# powerful.net
KiCad netlist of a schematic drawn in Altium Designer
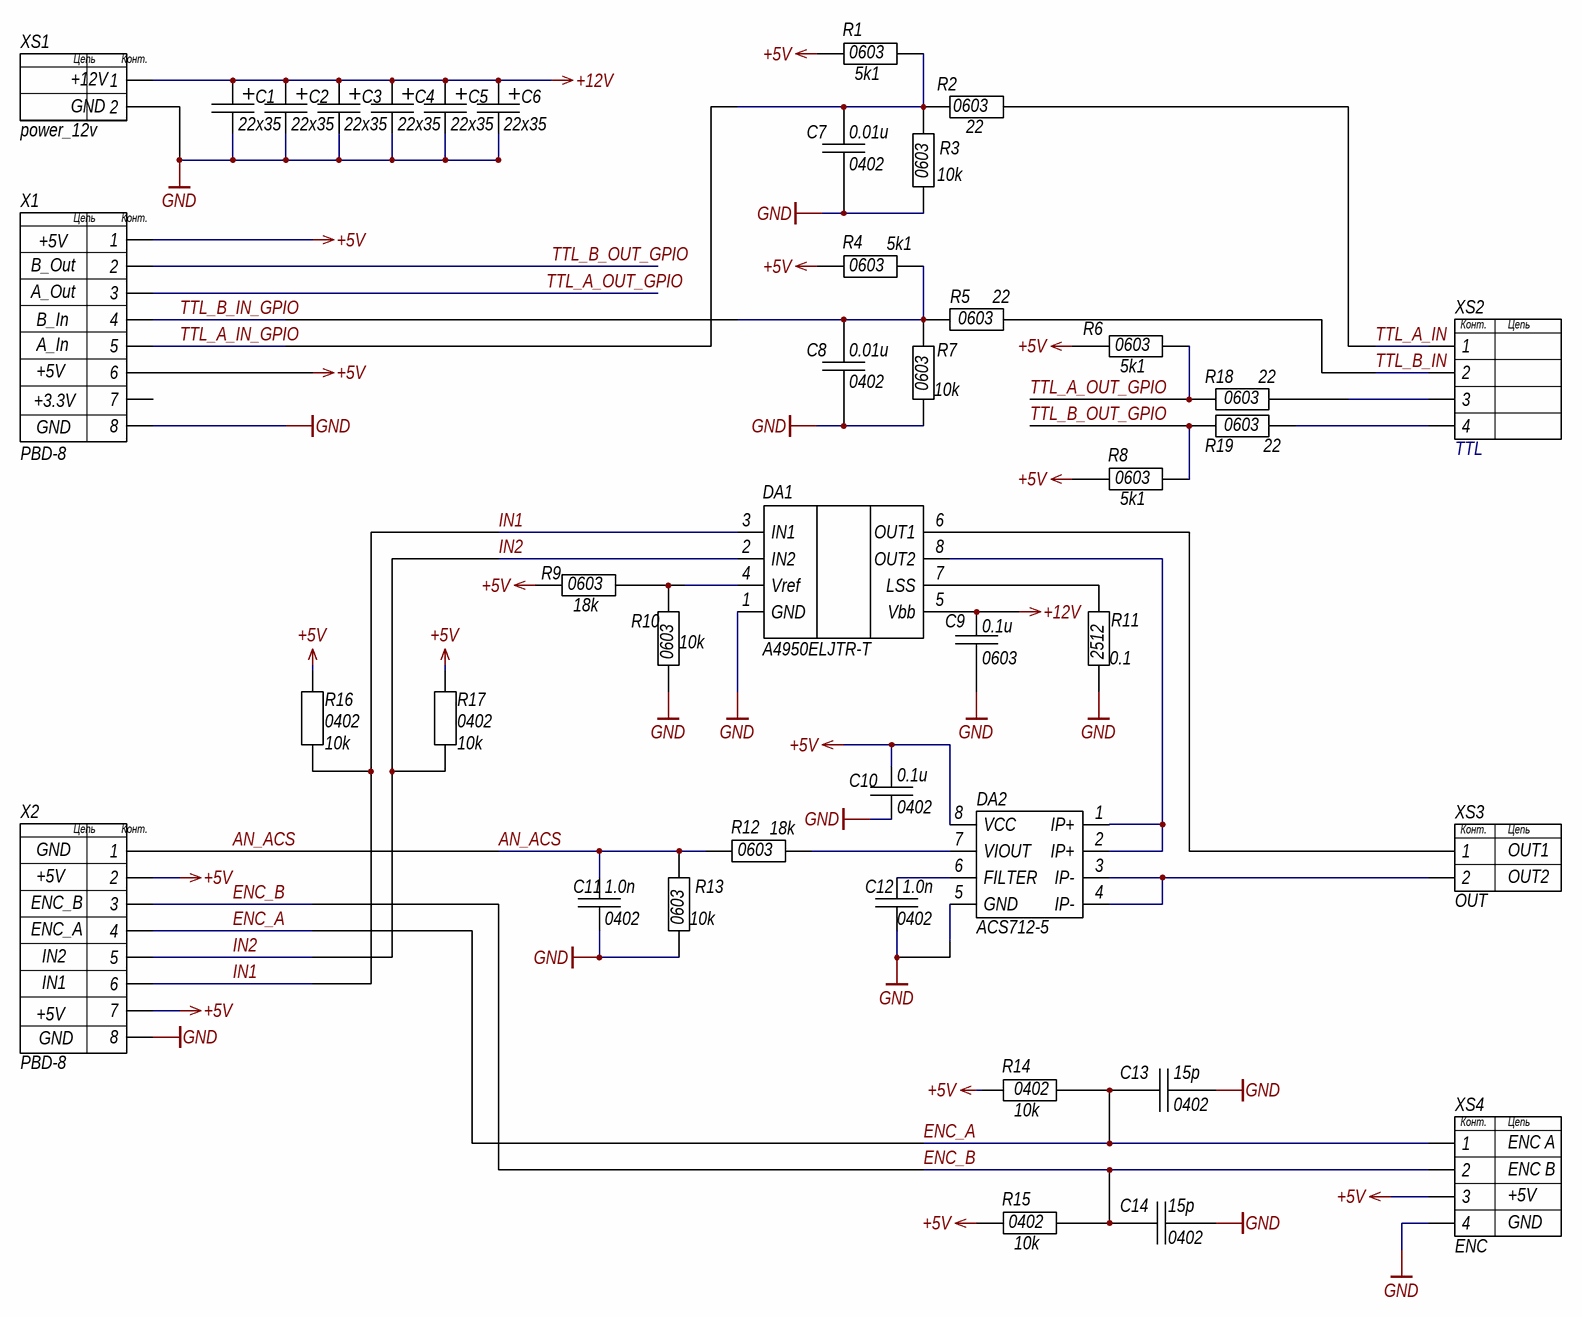
[diagram p0: powerful.SchDoc]

(export (version "E")
  (design (tool "Eeschema 10.0.6"))
  (components
    (comp (ref "C1")
      (value "22x35")
      (footprint "CASE D")
      (libsource (lib "Drive_GD32F") (part "Capacitor_pol"))
    )
    (comp (ref "C2")
      (value "22x35")
      (footprint "CASE D")
      (libsource (lib "Drive_GD32F") (part "Capacitor_pol"))
    )
    (comp (ref "C3")
      (value "22x35")
      (footprint "CASE D")
      (libsource (lib "Drive_GD32F") (part "Capacitor_pol"))
    )
    (comp (ref "C4")
      (value "22x35")
      (footprint "CASE D")
      (libsource (lib "Drive_GD32F") (part "Capacitor_pol"))
    )
    (comp (ref "C5")
      (value "22x35")
      (footprint "CASE D")
      (libsource (lib "Drive_GD32F") (part "Capacitor_pol"))
    )
    (comp (ref "C6")
      (value "22x35")
      (footprint "CASE D")
      (libsource (lib "Drive_GD32F") (part "Capacitor_pol"))
    )
    (comp (ref "C7")
      (value "0.01u")
      (footprint "0402_CAP")
      (fields (field (name "CASE") "0402"))
      (libsource (lib "Drive_GD32F") (part "Capacitor"))
    )
    (comp (ref "C8")
      (value "0.01u")
      (footprint "0402_CAP")
      (fields (field (name "CASE") "0402"))
      (libsource (lib "Drive_GD32F") (part "Capacitor"))
    )
    (comp (ref "C9")
      (value "0.1u")
      (footprint "0603_CAP")
      (fields (field (name "CASE") "0603"))
      (libsource (lib "Drive_GD32F") (part "Capacitor"))
    )
    (comp (ref "C10")
      (value "0.1u")
      (footprint "0402_CAP")
      (fields (field (name "CASE") "0402"))
      (libsource (lib "Drive_GD32F") (part "Capacitor"))
    )
    (comp (ref "C11")
      (value "1.0n")
      (footprint "0402_CAP")
      (fields (field (name "CASE") "0402"))
      (libsource (lib "Drive_GD32F") (part "Capacitor"))
    )
    (comp (ref "C12")
      (value "1.0n")
      (footprint "0402_CAP")
      (fields (field (name "CASE") "0402"))
      (libsource (lib "Drive_GD32F") (part "Capacitor"))
    )
    (comp (ref "C13")
      (value "15p")
      (footprint "0402_CAP")
      (fields (field (name "CASE") "0402"))
      (libsource (lib "Drive_GD32F") (part "Capacitor"))
    )
    (comp (ref "C14")
      (value "15p")
      (footprint "0402_CAP")
      (fields (field (name "CASE") "0402"))
      (libsource (lib "Drive_GD32F") (part "Capacitor"))
    )
    (comp (ref "DA1")
      (value "A4950ELJTR-T")
      (footprint "SOIC-8-ER")
      (libsource (lib "Drive_GD32F") (part "A4950ELJTR-T"))
    )
    (comp (ref "DA2")
      (value "ACS712-5")
      (footprint "SOIC-8")
      (libsource (lib "Drive_GD32F") (part "CurrentSensor_ACS712-5"))
    )
    (comp (ref "R1")
      (value "5k1")
      (footprint "0603_RES")
      (fields (field (name "CASE") "0603"))
      (libsource (lib "Drive_GD32F") (part "Resistor"))
    )
    (comp (ref "R2")
      (value "22")
      (footprint "0603_RES")
      (fields (field (name "POWER") "0603"))
      (libsource (lib "Drive_GD32F") (part "Resistor"))
    )
    (comp (ref "R3")
      (value "10k")
      (footprint "0603_RES")
      (fields (field (name "CASE") "0603"))
      (libsource (lib "Drive_GD32F") (part "Resistor"))
    )
    (comp (ref "R4")
      (value "5k1")
      (footprint "0603_RES")
      (fields (field (name "CASE") "0603"))
      (libsource (lib "Drive_GD32F") (part "Resistor"))
    )
    (comp (ref "R5")
      (value "22")
      (footprint "0603_RES")
      (fields (field (name "POWER") "0603"))
      (libsource (lib "Drive_GD32F") (part "Resistor"))
    )
    (comp (ref "R6")
      (value "5k1")
      (footprint "0603_RES")
      (fields (field (name "CASE") "0603"))
      (libsource (lib "Drive_GD32F") (part "Resistor"))
    )
    (comp (ref "R7")
      (value "10k")
      (footprint "0603_RES")
      (fields (field (name "CASE") "0603"))
      (libsource (lib "Drive_GD32F") (part "Resistor"))
    )
    (comp (ref "R8")
      (value "5k1")
      (footprint "0603_RES")
      (fields (field (name "CASE") "0603"))
      (libsource (lib "Drive_GD32F") (part "Resistor"))
    )
    (comp (ref "R9")
      (value "18k")
      (footprint "0603_RES")
      (fields (field (name "CASE") "0603"))
      (libsource (lib "Drive_GD32F") (part "Resistor"))
    )
    (comp (ref "R10")
      (value "10k")
      (footprint "0603_RES")
      (fields (field (name "CASE") "0603"))
      (libsource (lib "Drive_GD32F") (part "Resistor"))
    )
    (comp (ref "R11")
      (value "0.1")
      (footprint "2512_res")
      (fields (field (name "CASE") "2512"))
      (libsource (lib "Drive_GD32F") (part "Resistor"))
    )
    (comp (ref "R12")
      (value "18k")
      (footprint "0603_RES")
      (fields (field (name "CASE") "0603"))
      (libsource (lib "Drive_GD32F") (part "Resistor"))
    )
    (comp (ref "R13")
      (value "10k")
      (footprint "0603_RES")
      (fields (field (name "CASE") "0603"))
      (libsource (lib "Drive_GD32F") (part "Resistor"))
    )
    (comp (ref "R14")
      (value "10k")
      (footprint "0402_res")
      (fields (field (name "CASE") "0402"))
      (libsource (lib "Drive_GD32F") (part "Resistor"))
    )
    (comp (ref "R15")
      (value "10k")
      (footprint "0402_res")
      (fields (field (name "CASE") "0402"))
      (libsource (lib "Drive_GD32F") (part "Resistor"))
    )
    (comp (ref "R16")
      (value "10k")
      (footprint "0402_res")
      (fields (field (name "CASE") "0402"))
      (libsource (lib "Drive_GD32F") (part "Resistor"))
    )
    (comp (ref "R17")
      (value "10k")
      (footprint "0402_res")
      (fields (field (name "CASE") "0402"))
      (libsource (lib "Drive_GD32F") (part "Resistor"))
    )
    (comp (ref "R18")
      (value "22")
      (footprint "0603_RES")
      (fields (field (name "POWER") "0603"))
      (libsource (lib "Drive_GD32F") (part "Resistor"))
    )
    (comp (ref "R19")
      (value "22")
      (footprint "0603_RES")
      (fields (field (name "POWER") "0603"))
      (libsource (lib "Drive_GD32F") (part "Resistor"))
    )
    (comp (ref "X1")
      (value "PBD-8")
      (footprint "Header_8pin_2mm")
      (fields
        (field (name "PARAMETER 8") "GND")
        (field (name "PARAMETER 7") "+3.3V")
        (field (name "PARAMETER 6") "+5V")
        (field (name "PARAMETER 5") "A_In")
        (field (name "PARAMETER 4") "B_In")
        (field (name "PARAMETER 3") "A_Out")
        (field (name "PARAMETER 2") "B_Out")
        (field (name "PARAMETER 1") "+5V")
      )
      (libsource (lib "Drive_GD32F") (part "Connecor_8pin"))
    )
    (comp (ref "X2")
      (value "PBD-8")
      (footprint "Header_8pin_2mm")
      (fields
        (field (name "PARAMETER 8") "GND")
        (field (name "PARAMETER 7") "+5V")
        (field (name "PARAMETER 6") "IN1")
        (field (name "PARAMETER 5") "IN2")
        (field (name "PARAMETER 4") "ENC_A")
        (field (name "PARAMETER 3") "ENC_B")
        (field (name "PARAMETER 2") "+5V")
        (field (name "PARAMETER 1") "GND")
      )
      (libsource (lib "Drive_GD32F") (part "Connecor_8pin"))
    )
    (comp (ref "XS1")
      (value "power_12v")
      (footprint "STEP_2.54mm 2X1")
      (libsource (lib "Drive_GD32F") (part "power_12v"))
    )
    (comp (ref "XS2") (value "TTL") (footprint "PH4_2mm") (libsource (lib "Drive_GD32F") (part "TTL")))
    (comp (ref "XS3") (value "OUT") (footprint "step_2.54_2") (libsource (lib "Drive_GD32F") (part "OUT")))
    (comp (ref "XS4") (value "ENC") (footprint "PH4_2mm") (libsource (lib "Drive_GD32F") (part "ENC")))
  )
  (nets
    (net (code "1") (name "+5V") (class "Default")
      (node (ref "C10") (pin "2") (pintype "passive"))
      (node (ref "DA2") (pin "8") (pinfunction "VCC_8") (pintype "passive"))
      (node (ref "R1") (pin "2") (pinfunction "2_2") (pintype "passive"))
      (node (ref "R14") (pin "2") (pinfunction "2_2") (pintype "passive"))
      (node (ref "R15") (pin "2") (pinfunction "2_2") (pintype "passive"))
      (node (ref "R16") (pin "2") (pinfunction "2_2") (pintype "passive"))
      (node (ref "R17") (pin "2") (pinfunction "2_2") (pintype "passive"))
      (node (ref "R4") (pin "2") (pinfunction "2_2") (pintype "passive"))
      (node (ref "R6") (pin "2") (pinfunction "2_2") (pintype "passive"))
      (node (ref "R8") (pin "2") (pinfunction "2_2") (pintype "passive"))
      (node (ref "R9") (pin "2") (pinfunction "2_2") (pintype "passive"))
      (node (ref "X1") (pin "1") (pinfunction "1_1") (pintype "passive"))
      (node (ref "X1") (pin "6") (pinfunction "6_6") (pintype "passive"))
      (node (ref "X2") (pin "2") (pinfunction "2_2") (pintype "passive"))
      (node (ref "X2") (pin "7") (pinfunction "7_7") (pintype "passive"))
      (node (ref "XS4") (pin "3") (pinfunction "3_3") (pintype "passive"))
    )
    (net (code "2") (name "+12V") (class "Default")
      (node (ref "C1") (pin "1") (pintype "passive"))
      (node (ref "C2") (pin "1") (pintype "passive"))
      (node (ref "C3") (pin "1") (pintype "passive"))
      (node (ref "C4") (pin "1") (pintype "passive"))
      (node (ref "C5") (pin "1") (pintype "passive"))
      (node (ref "C6") (pin "1") (pintype "passive"))
      (node (ref "C9") (pin "1") (pintype "passive"))
      (node (ref "DA1") (pin "5") (pinfunction "Vbb_5") (pintype "passive"))
      (node (ref "XS1") (pin "1") (pinfunction "1_1") (pintype "passive"))
    )
    (net (code "3") (name "/AN_ACS") (class "Default")
      (node (ref "C11") (pin "2") (pintype "passive"))
      (node (ref "R12") (pin "1") (pinfunction "1_1") (pintype "passive"))
      (node (ref "R13") (pin "2") (pinfunction "2_2") (pintype "passive"))
      (node (ref "X2") (pin "1") (pinfunction "1_1") (pintype "passive"))
    )
    (net (code "4") (name "/ENC_A") (class "Default")
      (node (ref "C13") (pin "1") (pintype "passive"))
      (node (ref "R14") (pin "1") (pinfunction "1_1") (pintype "passive"))
      (node (ref "X2") (pin "4") (pinfunction "4_4") (pintype "passive"))
      (node (ref "XS4") (pin "1") (pinfunction "1_1") (pintype "passive"))
    )
    (net (code "5") (name "/ENC_B") (class "Default")
      (node (ref "C14") (pin "2") (pintype "passive"))
      (node (ref "R15") (pin "1") (pinfunction "1_1") (pintype "passive"))
      (node (ref "X2") (pin "3") (pinfunction "3_3") (pintype "passive"))
      (node (ref "XS4") (pin "2") (pinfunction "2_2") (pintype "passive"))
    )
    (net (code "6") (name "/IN1") (class "Default")
      (node (ref "DA1") (pin "3") (pinfunction "IN1_3") (pintype "passive"))
      (node (ref "R16") (pin "1") (pinfunction "1_1") (pintype "passive"))
      (node (ref "X2") (pin "6") (pinfunction "6_6") (pintype "passive"))
    )
    (net (code "7") (name "/IN2") (class "Default")
      (node (ref "DA1") (pin "2") (pinfunction "IN2_2") (pintype "passive"))
      (node (ref "R17") (pin "1") (pinfunction "1_1") (pintype "passive"))
      (node (ref "X2") (pin "5") (pinfunction "5_5") (pintype "passive"))
    )
    (net (code "8") (name "/TTL_A_IN") (class "Default")
      (node (ref "R2") (pin "2") (pinfunction "2_2") (pintype "passive"))
      (node (ref "XS2") (pin "1") (pinfunction "1_1") (pintype "passive"))
    )
    (net (code "9") (name "/TTL_A_IN_GPIO") (class "Default")
      (node (ref "C7") (pin "2") (pintype "passive"))
      (node (ref "R1") (pin "1") (pinfunction "1_1") (pintype "passive"))
      (node (ref "R2") (pin "1") (pinfunction "1_1") (pintype "passive"))
      (node (ref "R3") (pin "2") (pinfunction "2_2") (pintype "passive"))
      (node (ref "X1") (pin "5") (pinfunction "5_5") (pintype "passive"))
    )
    (net (code "10") (name "/TTL_A_OUT_GPIO") (class "Default")
      (node (ref "R18") (pin "1") (pinfunction "1_1") (pintype "passive"))
      (node (ref "R6") (pin "1") (pinfunction "1_1") (pintype "passive"))
      (node (ref "X1") (pin "3") (pinfunction "3_3") (pintype "passive"))
    )
    (net (code "11") (name "/TTL_B_IN") (class "Default")
      (node (ref "R5") (pin "2") (pinfunction "2_2") (pintype "passive"))
      (node (ref "XS2") (pin "2") (pinfunction "2_2") (pintype "passive"))
    )
    (net (code "12") (name "/TTL_B_IN_GPIO") (class "Default")
      (node (ref "C8") (pin "2") (pintype "passive"))
      (node (ref "R4") (pin "1") (pinfunction "1_1") (pintype "passive"))
      (node (ref "R5") (pin "1") (pinfunction "1_1") (pintype "passive"))
      (node (ref "R7") (pin "2") (pinfunction "2_2") (pintype "passive"))
      (node (ref "X1") (pin "4") (pinfunction "4_4") (pintype "passive"))
    )
    (net (code "13") (name "/TTL_B_OUT_GPIO") (class "Default")
      (node (ref "R19") (pin "1") (pinfunction "1_1") (pintype "passive"))
      (node (ref "R8") (pin "1") (pinfunction "1_1") (pintype "passive"))
      (node (ref "X1") (pin "2") (pinfunction "2_2") (pintype "passive"))
    )
    (net (code "14") (name "GND") (class "Default")
      (node (ref "C1") (pin "2") (pintype "passive"))
      (node (ref "C10") (pin "1") (pintype "passive"))
      (node (ref "C11") (pin "1") (pintype "passive"))
      (node (ref "C12") (pin "1") (pintype "passive"))
      (node (ref "C13") (pin "2") (pintype "passive"))
      (node (ref "C14") (pin "1") (pintype "passive"))
      (node (ref "C2") (pin "2") (pintype "passive"))
      (node (ref "C3") (pin "2") (pintype "passive"))
      (node (ref "C4") (pin "2") (pintype "passive"))
      (node (ref "C5") (pin "2") (pintype "passive"))
      (node (ref "C6") (pin "2") (pintype "passive"))
      (node (ref "C7") (pin "1") (pintype "passive"))
      (node (ref "C8") (pin "1") (pintype "passive"))
      (node (ref "C9") (pin "2") (pintype "passive"))
      (node (ref "DA1") (pin "1") (pinfunction "GND_1") (pintype "passive"))
      (node (ref "DA2") (pin "5") (pinfunction "GND_5") (pintype "passive"))
      (node (ref "R10") (pin "1") (pinfunction "1_1") (pintype "passive"))
      (node (ref "R11") (pin "2") (pinfunction "2_2") (pintype "passive"))
      (node (ref "R13") (pin "1") (pinfunction "1_1") (pintype "passive"))
      (node (ref "R3") (pin "1") (pinfunction "1_1") (pintype "passive"))
      (node (ref "R7") (pin "1") (pinfunction "1_1") (pintype "passive"))
      (node (ref "X1") (pin "8") (pinfunction "8_8") (pintype "passive"))
      (node (ref "X2") (pin "8") (pinfunction "8_8") (pintype "passive"))
      (node (ref "XS1") (pin "2") (pinfunction "2_2") (pintype "passive"))
      (node (ref "XS4") (pin "4") (pinfunction "4_4") (pintype "passive"))
    )
    (net (code "15") (name "Net-(DA1-LSS)") (class "Default")
      (node (ref "DA1") (pin "7") (pinfunction "LSS_7") (pintype "passive"))
      (node (ref "R11") (pin "1") (pinfunction "1_1") (pintype "passive"))
    )
    (net (code "16") (name "Net-(DA1-OUT1)") (class "Default")
      (node (ref "DA1") (pin "6") (pinfunction "OUT1_6") (pintype "passive"))
      (node (ref "XS3") (pin "1") (pinfunction "1_1") (pintype "passive"))
    )
    (net (code "17") (name "Net-(DA1-OUT2)") (class "Default")
      (node (ref "DA1") (pin "8") (pinfunction "OUT2_8") (pintype "passive"))
      (node (ref "DA2") (pin "1") (pinfunction "IP+_1") (pintype "passive"))
      (node (ref "DA2") (pin "2") (pinfunction "IP+_2") (pintype "passive"))
    )
    (net (code "18") (name "Net-(DA1-Vref)") (class "Default")
      (node (ref "DA1") (pin "4") (pinfunction "Vref_4") (pintype "passive"))
      (node (ref "R10") (pin "2") (pinfunction "2_2") (pintype "passive"))
      (node (ref "R9") (pin "1") (pinfunction "1_1") (pintype "passive"))
    )
    (net (code "19") (name "Net-(DA2-FILTER)") (class "Default")
      (node (ref "C12") (pin "2") (pintype "passive"))
      (node (ref "DA2") (pin "6") (pinfunction "FILTER_6") (pintype "passive"))
    )
    (net (code "20") (name "Net-(DA2-IP--Pad3)") (class "Default")
      (node (ref "DA2") (pin "3") (pinfunction "IP-_3") (pintype "passive"))
      (node (ref "DA2") (pin "4") (pinfunction "IP-_4") (pintype "passive"))
      (node (ref "XS3") (pin "2") (pinfunction "2_2") (pintype "passive"))
    )
    (net (code "21") (name "Net-(DA2-VIOUT)") (class "Default")
      (node (ref "DA2") (pin "7") (pinfunction "VIOUT_7") (pintype "passive"))
      (node (ref "R12") (pin "2") (pinfunction "2_2") (pintype "passive"))
    )
    (net (code "22") (name "Net-(R18-Pad2)") (class "Default")
      (node (ref "R18") (pin "2") (pinfunction "2_2") (pintype "passive"))
      (node (ref "XS2") (pin "3") (pinfunction "3_3") (pintype "passive"))
    )
    (net (code "23") (name "Net-(R19-Pad2)") (class "Default")
      (node (ref "R19") (pin "2") (pinfunction "2_2") (pintype "passive"))
      (node (ref "XS2") (pin "4") (pinfunction "4_4") (pintype "passive"))
    )
    (net (code "24") (name "unconnected-(X1-Pad7)") (class "Default")
      (node (ref "X1") (pin "7") (pinfunction "7_7") (pintype "passive"))
    )
  )
)
